# driver.net
KiCad netlist of a schematic drawn in Altium Designer
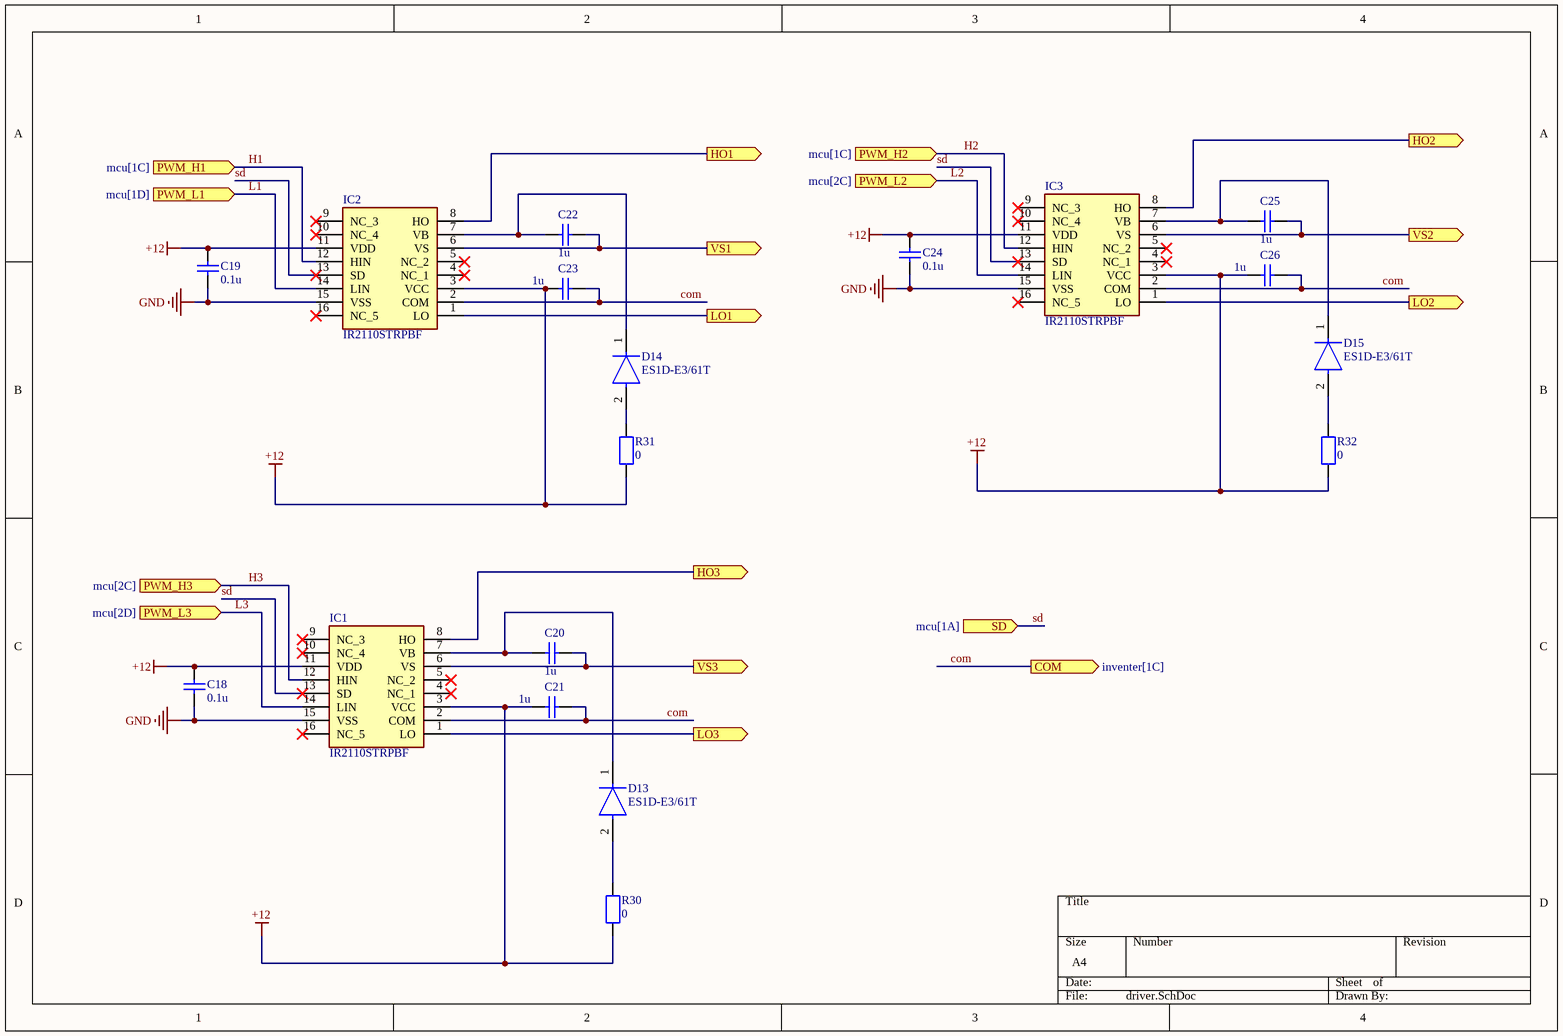
[diagram p0: driver.SchDoc]

(export (version "E")
  (design (tool "Eeschema 10.0.6"))
  (components
    (comp (ref "C18")
      (value "0.1u")
      (footprint "CAPC2012X06N")
      (description "Конденсатор керамический smd 0.01 мкФ NPO 50В 5%")
      (fields (field (name "Comment") "CAP"))
      (libsource (lib "Capacitors") (part "CAP"))
    )
    (comp (ref "C19")
      (value "0.1u")
      (footprint "CAPC2012X06N")
      (description "Конденсатор керамический smd 0.01 мкФ NPO 50В 5%")
      (fields (field (name "Comment") "CAP"))
      (libsource (lib "Capacitors") (part "CAP"))
    )
    (comp (ref "C20")
      (value "1u")
      (footprint "CAPC2012X06N")
      (description "Конденсатор керамический smd 1 мкФ X7R 10% 50В 0805")
      (fields (field (name "Comment") "CAP"))
      (libsource (lib "Capacitors") (part "CAP"))
    )
    (comp (ref "C21")
      (value "1u")
      (footprint "CAPC2012X06N")
      (description "Конденсатор керамический smd 1 мкФ X7R 10% 50В 0805")
      (fields (field (name "Comment") "CAP"))
      (libsource (lib "Capacitors") (part "CAP"))
    )
    (comp (ref "C22")
      (value "1u")
      (footprint "CAPC2012X06N")
      (description "Конденсатор керамический smd 1 мкФ X7R 10% 50В 0805")
      (fields (field (name "Comment") "CAP"))
      (libsource (lib "Capacitors") (part "CAP"))
    )
    (comp (ref "C23")
      (value "1u")
      (footprint "CAPC2012X06N")
      (description "Конденсатор керамический smd 1 мкФ X7R 10% 50В 0805")
      (fields (field (name "Comment") "CAP"))
      (libsource (lib "Capacitors") (part "CAP"))
    )
    (comp (ref "C24")
      (value "0.1u")
      (footprint "CAPC2012X06N")
      (description "Конденсатор керамический smd 0.01 мкФ NPO 50В 5%")
      (fields (field (name "Comment") "CAP"))
      (libsource (lib "Capacitors") (part "CAP"))
    )
    (comp (ref "C25")
      (value "1u")
      (footprint "CAPC2012X06N")
      (description "Конденсатор керамический smd 1 мкФ X7R 10% 50В 0805")
      (fields (field (name "Comment") "CAP"))
      (libsource (lib "Capacitors") (part "CAP"))
    )
    (comp (ref "C26")
      (value "1u")
      (footprint "CAPC2012X06N")
      (description "Конденсатор керамический smd 1 мкФ X7R 10% 50В 0805")
      (fields (field (name "Comment") "CAP"))
      (libsource (lib "Capacitors") (part "CAP"))
    )
    (comp (ref "D13")
      (value "ES1D-E3/61T")
      (footprint "FP-95400-MFG")
      (description "DIODE GEN PURP 200V 1A DO214AC")
      (fields
        (field (name "MANUFACTURER") "Vishay")
        (field (name "OCTOPART") "https://octopart.com/es1d-e3%2F61t-vishay-39550266")
      )
      (libsource (lib "Altium Content Vault") (part "d7152d700b627762746794eb795d46e"))
    )
    (comp (ref "D14")
      (value "ES1D-E3/61T")
      (footprint "FP-95400-MFG")
      (description "DIODE GEN PURP 200V 1A DO214AC")
      (fields
        (field (name "MANUFACTURER") "Vishay")
        (field (name "OCTOPART") "https://octopart.com/es1d-e3%2F61t-vishay-39550266")
      )
      (libsource (lib "Altium Content Vault") (part "d7152d700b627762746794eb795d46e"))
    )
    (comp (ref "D15")
      (value "ES1D-E3/61T")
      (footprint "FP-95400-MFG")
      (description "DIODE GEN PURP 200V 1A DO214AC")
      (fields
        (field (name "MANUFACTURER") "Vishay")
        (field (name "OCTOPART") "https://octopart.com/es1d-e3%2F61t-vishay-39550266")
      )
      (libsource (lib "Altium Content Vault") (part "d7152d700b627762746794eb795d46e"))
    )
    (comp (ref "IC1")
      (value "IR2110STRPBF")
      (footprint "SamacLib:SOIC127P1032X265-16N")
      (description "IR2110STRPBF, Полумостовой драйвер HIGH/LOW SIDE")
      (fields (field (name "MOUSER PART NUMBER") "942-IR2110STRPBF"))
      (libsource (lib "SamacSys") (part "IR2110STRPBF"))
    )
    (comp (ref "IC2")
      (value "IR2110STRPBF")
      (footprint "SamacLib:SOIC127P1032X265-16N")
      (description "IR2110STRPBF, Полумостовой драйвер HIGH/LOW SIDE")
      (fields (field (name "MOUSER PART NUMBER") "942-IR2110STRPBF"))
      (libsource (lib "SamacSys") (part "IR2110STRPBF"))
    )
    (comp (ref "IC3")
      (value "IR2110STRPBF")
      (footprint "SamacLib:SOIC127P1032X265-16N")
      (description "IR2110STRPBF, Полумостовой драйвер HIGH/LOW SIDE")
      (fields (field (name "MOUSER PART NUMBER") "942-IR2110STRPBF"))
      (libsource (lib "SamacSys") (part "IR2110STRPBF"))
    )
    (comp (ref "R30")
      (value "0")
      (footprint "RESC3016X06N")
      (fields (field (name "Comment") "Resistor"))
      (libsource (lib "Resistor") (part "Resistor"))
    )
    (comp (ref "R31")
      (value "0")
      (footprint "RESC3016X06N")
      (fields (field (name "Comment") "Resistor"))
      (libsource (lib "Resistor") (part "Resistor"))
    )
    (comp (ref "R32")
      (value "0")
      (footprint "RESC3016X06N")
      (fields (field (name "Comment") "Resistor"))
      (libsource (lib "Resistor") (part "Resistor"))
    )
  )
  (nets
    (net (code "1") (name "+12") (class "Default")
      (node (ref "C18") (pin "1") (pinfunction "2_1") (pintype "passive"))
      (node (ref "C19") (pin "1") (pinfunction "2_1") (pintype "passive"))
      (node (ref "C21") (pin "2") (pinfunction "1_2") (pintype "passive"))
      (node (ref "C23") (pin "2") (pinfunction "1_2") (pintype "passive"))
      (node (ref "C24") (pin "1") (pinfunction "2_1") (pintype "passive"))
      (node (ref "C26") (pin "2") (pinfunction "1_2") (pintype "passive"))
      (node (ref "IC1") (pin "11") (pinfunction "VDD_11") (pintype "passive"))
      (node (ref "IC1") (pin "3") (pinfunction "VCC_3") (pintype "passive"))
      (node (ref "IC2") (pin "11") (pinfunction "VDD_11") (pintype "passive"))
      (node (ref "IC2") (pin "3") (pinfunction "VCC_3") (pintype "passive"))
      (node (ref "IC3") (pin "11") (pinfunction "VDD_11") (pintype "passive"))
      (node (ref "IC3") (pin "3") (pinfunction "VCC_3") (pintype "passive"))
      (node (ref "R30") (pin "1") (pinfunction "*_1") (pintype "passive"))
      (node (ref "R31") (pin "1") (pinfunction "*_1") (pintype "passive"))
      (node (ref "R32") (pin "1") (pinfunction "*_1") (pintype "passive"))
    )
    (net (code "2") (name "/H1") (class "Default")
      (node (ref "IC2") (pin "12") (pinfunction "HIN_12") (pintype "passive"))
    )
    (net (code "3") (name "/H2") (class "Default")
      (node (ref "IC3") (pin "12") (pinfunction "HIN_12") (pintype "passive"))
    )
    (net (code "4") (name "/H3") (class "Default")
      (node (ref "IC1") (pin "12") (pinfunction "HIN_12") (pintype "passive"))
    )
    (net (code "5") (name "/HO1") (class "Default")
      (node (ref "IC2") (pin "8") (pinfunction "HO_8") (pintype "passive"))
    )
    (net (code "6") (name "/HO2") (class "Default")
      (node (ref "IC3") (pin "8") (pinfunction "HO_8") (pintype "passive"))
    )
    (net (code "7") (name "/HO3") (class "Default")
      (node (ref "IC1") (pin "8") (pinfunction "HO_8") (pintype "passive"))
    )
    (net (code "8") (name "/L1") (class "Default")
      (node (ref "IC2") (pin "14") (pinfunction "LIN_14") (pintype "passive"))
    )
    (net (code "9") (name "/L2") (class "Default")
      (node (ref "IC3") (pin "14") (pinfunction "LIN_14") (pintype "passive"))
    )
    (net (code "10") (name "/L3") (class "Default")
      (node (ref "IC1") (pin "14") (pinfunction "LIN_14") (pintype "passive"))
    )
    (net (code "11") (name "/LO1") (class "Default")
      (node (ref "IC2") (pin "1") (pinfunction "LO_1") (pintype "passive"))
    )
    (net (code "12") (name "/LO2") (class "Default")
      (node (ref "IC3") (pin "1") (pinfunction "LO_1") (pintype "passive"))
    )
    (net (code "13") (name "/LO3") (class "Default")
      (node (ref "IC1") (pin "1") (pinfunction "LO_1") (pintype "passive"))
    )
    (net (code "14") (name "/VS1") (class "Default")
      (node (ref "C22") (pin "2") (pinfunction "1_2") (pintype "passive"))
      (node (ref "IC2") (pin "6") (pinfunction "VS_6") (pintype "passive"))
    )
    (net (code "15") (name "/VS2") (class "Default")
      (node (ref "C25") (pin "2") (pinfunction "1_2") (pintype "passive"))
      (node (ref "IC3") (pin "6") (pinfunction "VS_6") (pintype "passive"))
    )
    (net (code "16") (name "/VS3") (class "Default")
      (node (ref "C20") (pin "2") (pinfunction "1_2") (pintype "passive"))
      (node (ref "IC1") (pin "6") (pinfunction "VS_6") (pintype "passive"))
    )
    (net (code "17") (name "/com") (class "Default")
      (node (ref "C21") (pin "1") (pinfunction "2_1") (pintype "passive"))
      (node (ref "C23") (pin "1") (pinfunction "2_1") (pintype "passive"))
      (node (ref "C26") (pin "1") (pinfunction "2_1") (pintype "passive"))
      (node (ref "IC1") (pin "2") (pinfunction "COM_2") (pintype "passive"))
      (node (ref "IC2") (pin "2") (pinfunction "COM_2") (pintype "passive"))
      (node (ref "IC3") (pin "2") (pinfunction "COM_2") (pintype "passive"))
    )
    (net (code "18") (name "/sd") (class "Default")
      (node (ref "IC1") (pin "13") (pinfunction "SD_13") (pintype "passive"))
      (node (ref "IC2") (pin "13") (pinfunction "SD_13") (pintype "passive"))
      (node (ref "IC3") (pin "13") (pinfunction "SD_13") (pintype "passive"))
    )
    (net (code "19") (name "GND") (class "Default")
      (node (ref "C18") (pin "2") (pinfunction "1_2") (pintype "passive"))
      (node (ref "C19") (pin "2") (pinfunction "1_2") (pintype "passive"))
      (node (ref "C24") (pin "2") (pinfunction "1_2") (pintype "passive"))
      (node (ref "IC1") (pin "15") (pinfunction "VSS_15") (pintype "passive"))
      (node (ref "IC2") (pin "15") (pinfunction "VSS_15") (pintype "passive"))
      (node (ref "IC3") (pin "15") (pinfunction "VSS_15") (pintype "passive"))
    )
    (net (code "20") (name "Net-(C20-2)") (class "Default")
      (node (ref "C20") (pin "1") (pinfunction "2_1") (pintype "passive"))
      (node (ref "D13") (pin "1") (pinfunction "C_1") (pintype "passive"))
      (node (ref "IC1") (pin "7") (pinfunction "VB_7") (pintype "passive"))
    )
    (net (code "21") (name "Net-(C22-2)") (class "Default")
      (node (ref "C22") (pin "1") (pinfunction "2_1") (pintype "passive"))
      (node (ref "D14") (pin "1") (pinfunction "C_1") (pintype "passive"))
      (node (ref "IC2") (pin "7") (pinfunction "VB_7") (pintype "passive"))
    )
    (net (code "22") (name "Net-(C25-2)") (class "Default")
      (node (ref "C25") (pin "1") (pinfunction "2_1") (pintype "passive"))
      (node (ref "D15") (pin "1") (pinfunction "C_1") (pintype "passive"))
      (node (ref "IC3") (pin "7") (pinfunction "VB_7") (pintype "passive"))
    )
    (net (code "23") (name "Net-(D13-A)") (class "Default")
      (node (ref "D13") (pin "2") (pinfunction "A_2") (pintype "passive"))
      (node (ref "R30") (pin "2") (pinfunction "*_2") (pintype "passive"))
    )
    (net (code "24") (name "Net-(D14-A)") (class "Default")
      (node (ref "D14") (pin "2") (pinfunction "A_2") (pintype "passive"))
      (node (ref "R31") (pin "2") (pinfunction "*_2") (pintype "passive"))
    )
    (net (code "25") (name "Net-(D15-A)") (class "Default")
      (node (ref "D15") (pin "2") (pinfunction "A_2") (pintype "passive"))
      (node (ref "R32") (pin "2") (pinfunction "*_2") (pintype "passive"))
    )
    (net (code "26") (name "unconnected-(IC1-NC_1-Pad4)") (class "Default")
      (node (ref "IC1") (pin "4") (pinfunction "NC_1_4") (pintype "passive+no_connect"))
    )
    (net (code "27") (name "unconnected-(IC1-NC_2-Pad5)") (class "Default")
      (node (ref "IC1") (pin "5") (pinfunction "NC_2_5") (pintype "passive+no_connect"))
    )
    (net (code "28") (name "unconnected-(IC1-NC_3-Pad9)") (class "Default")
      (node (ref "IC1") (pin "9") (pinfunction "NC_3_9") (pintype "passive+no_connect"))
    )
    (net (code "29") (name "unconnected-(IC1-NC_4-Pad10)") (class "Default")
      (node (ref "IC1") (pin "10") (pinfunction "NC_4_10") (pintype "passive+no_connect"))
    )
    (net (code "30") (name "unconnected-(IC1-NC_5-Pad16)") (class "Default")
      (node (ref "IC1") (pin "16") (pinfunction "NC_5_16") (pintype "passive+no_connect"))
    )
    (net (code "31") (name "unconnected-(IC2-NC_1-Pad4)") (class "Default")
      (node (ref "IC2") (pin "4") (pinfunction "NC_1_4") (pintype "passive+no_connect"))
    )
    (net (code "32") (name "unconnected-(IC2-NC_2-Pad5)") (class "Default")
      (node (ref "IC2") (pin "5") (pinfunction "NC_2_5") (pintype "passive+no_connect"))
    )
    (net (code "33") (name "unconnected-(IC2-NC_3-Pad9)") (class "Default")
      (node (ref "IC2") (pin "9") (pinfunction "NC_3_9") (pintype "passive+no_connect"))
    )
    (net (code "34") (name "unconnected-(IC2-NC_4-Pad10)") (class "Default")
      (node (ref "IC2") (pin "10") (pinfunction "NC_4_10") (pintype "passive+no_connect"))
    )
    (net (code "35") (name "unconnected-(IC2-NC_5-Pad16)") (class "Default")
      (node (ref "IC2") (pin "16") (pinfunction "NC_5_16") (pintype "passive+no_connect"))
    )
    (net (code "36") (name "unconnected-(IC3-NC_1-Pad4)") (class "Default")
      (node (ref "IC3") (pin "4") (pinfunction "NC_1_4") (pintype "passive+no_connect"))
    )
    (net (code "37") (name "unconnected-(IC3-NC_2-Pad5)") (class "Default")
      (node (ref "IC3") (pin "5") (pinfunction "NC_2_5") (pintype "passive+no_connect"))
    )
    (net (code "38") (name "unconnected-(IC3-NC_3-Pad9)") (class "Default")
      (node (ref "IC3") (pin "9") (pinfunction "NC_3_9") (pintype "passive+no_connect"))
    )
    (net (code "39") (name "unconnected-(IC3-NC_4-Pad10)") (class "Default")
      (node (ref "IC3") (pin "10") (pinfunction "NC_4_10") (pintype "passive+no_connect"))
    )
    (net (code "40") (name "unconnected-(IC3-NC_5-Pad16)") (class "Default")
      (node (ref "IC3") (pin "16") (pinfunction "NC_5_16") (pintype "passive+no_connect"))
    )
  )
)
